# LNA_BFU500.net
KiCad netlist of a schematic drawn in Altium Designer
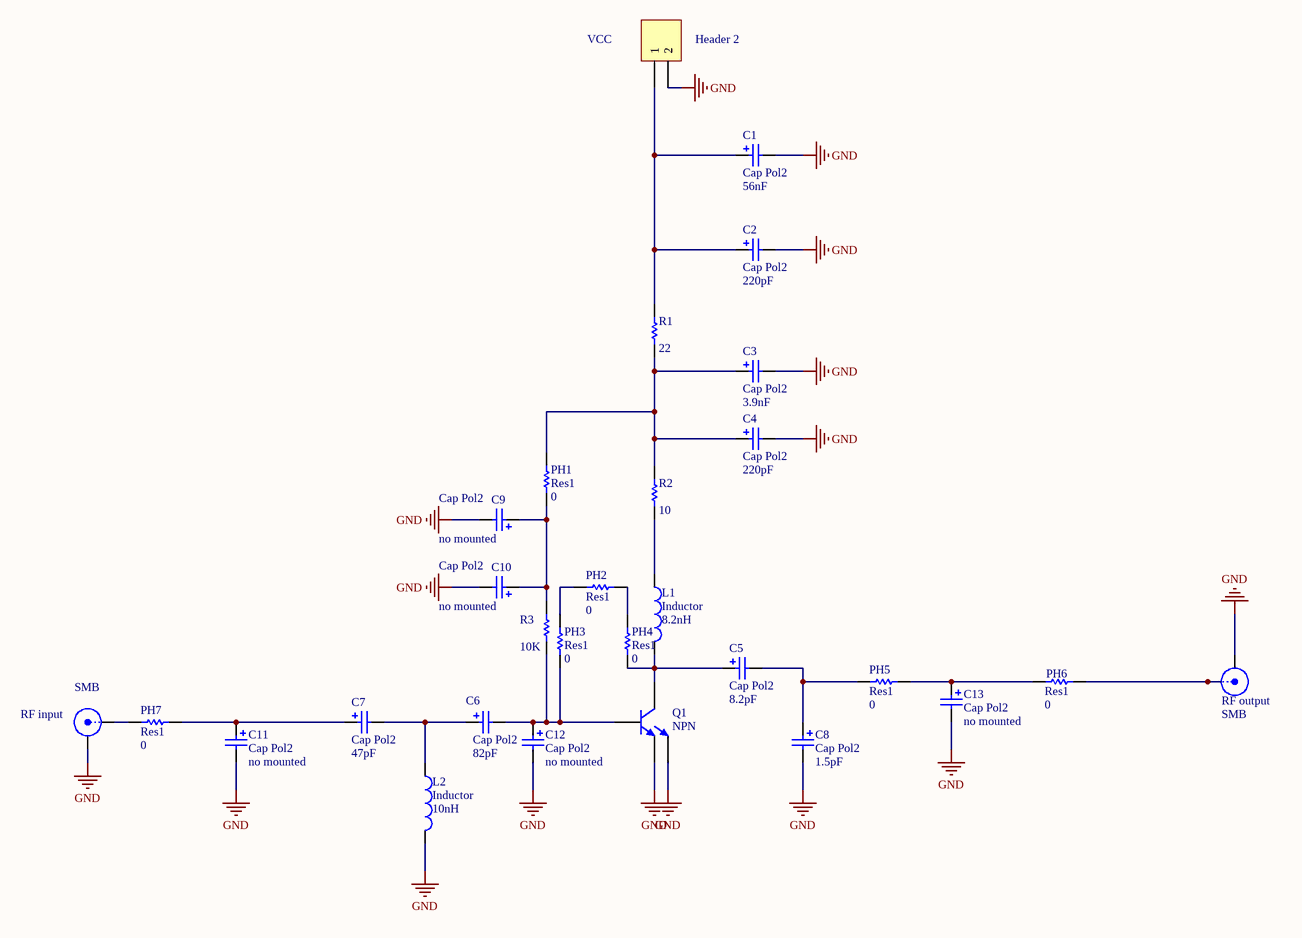
[diagram p0: LNA_BFU500.SchDoc]

(export (version "E")
  (design (tool "Eeschema 10.0.6"))
  (components
    (comp (ref "C1")
      (value "Cap Pol2")
      (footprint "6-0805_N")
      (description "Polarized Capacitor (Axial)")
      (fields (field (name "ALTIUM_VALUE") "56nF") (field (name "PUBLISHER") "Altium Limited"))
      (libsource (lib "PCB_Project") (part "Cap Pol2_1"))
    )
    (comp (ref "C2")
      (value "Cap Pol2")
      (footprint "6-0805_N")
      (description "Polarized Capacitor (Axial)")
      (fields (field (name "ALTIUM_VALUE") "220pF") (field (name "PUBLISHER") "Altium Limited"))
      (libsource (lib "PCB_Project") (part "Cap Pol2_1"))
    )
    (comp (ref "C3")
      (value "Cap Pol2")
      (footprint "6-0805_N")
      (description "Polarized Capacitor (Axial)")
      (fields (field (name "ALTIUM_VALUE") "3.9nF") (field (name "PUBLISHER") "Altium Limited"))
      (libsource (lib "PCB_Project") (part "Cap Pol2_1"))
    )
    (comp (ref "C4")
      (value "Cap Pol2")
      (footprint "6-0805_N")
      (description "Polarized Capacitor (Axial)")
      (fields (field (name "ALTIUM_VALUE") "220pF") (field (name "PUBLISHER") "Altium Limited"))
      (libsource (lib "PCB_Project") (part "Cap Pol2_1"))
    )
    (comp (ref "C5")
      (value "Cap Pol2")
      (footprint "6-0805_N")
      (description "Polarized Capacitor (Axial)")
      (fields (field (name "ALTIUM_VALUE") "8.2pF") (field (name "PUBLISHER") "Altium Limited"))
      (libsource (lib "PCB_Project") (part "Cap Pol2_1"))
    )
    (comp (ref "C6")
      (value "Cap Pol2")
      (footprint "6-0805_N")
      (description "Polarized Capacitor (Axial)")
      (fields (field (name "ALTIUM_VALUE") "82pF") (field (name "PUBLISHER") "Altium Limited"))
      (libsource (lib "PCB_Project") (part "Cap Pol2_1"))
    )
    (comp (ref "C7")
      (value "Cap Pol2")
      (footprint "6-0805_N")
      (description "Polarized Capacitor (Axial)")
      (fields (field (name "ALTIUM_VALUE") "47pF") (field (name "PUBLISHER") "Altium Limited"))
      (libsource (lib "PCB_Project") (part "Cap Pol2_1"))
    )
    (comp (ref "C8")
      (value "Cap Pol2")
      (footprint "6-0805_N")
      (description "Polarized Capacitor (Axial)")
      (fields (field (name "ALTIUM_VALUE") "1.5pF") (field (name "PUBLISHER") "Altium Limited"))
      (libsource (lib "PCB_Project") (part "Cap Pol2_1"))
    )
    (comp (ref "C9")
      (value "Cap Pol2")
      (footprint "6-0805_N")
      (description "Polarized Capacitor (Axial)")
      (fields (field (name "ALTIUM_VALUE") "no mounted") (field (name "PUBLISHER") "Altium Limited"))
      (libsource (lib "LNA_BFU550") (part "Cap Pol2_7"))
    )
    (comp (ref "C10")
      (value "Cap Pol2")
      (footprint "6-0805_N")
      (description "Polarized Capacitor (Axial)")
      (fields (field (name "ALTIUM_VALUE") "no mounted") (field (name "PUBLISHER") "Altium Limited"))
      (libsource (lib "LNA_BFU550") (part "Cap Pol2_7"))
    )
    (comp (ref "C11")
      (value "Cap Pol2")
      (footprint "6-0805_N")
      (description "Polarized Capacitor (Axial)")
      (fields (field (name "ALTIUM_VALUE") "no mounted") (field (name "PUBLISHER") "Altium Limited"))
      (libsource (lib "LNA_BFU550") (part "Cap Pol2_7"))
    )
    (comp (ref "C12")
      (value "Cap Pol2")
      (footprint "6-0805_N")
      (description "Polarized Capacitor (Axial)")
      (fields (field (name "ALTIUM_VALUE") "no mounted") (field (name "PUBLISHER") "Altium Limited"))
      (libsource (lib "LNA_BFU550") (part "Cap Pol2_7"))
    )
    (comp (ref "C13")
      (value "Cap Pol2")
      (footprint "6-0805_N")
      (description "Polarized Capacitor (Axial)")
      (fields (field (name "ALTIUM_VALUE") "no mounted") (field (name "PUBLISHER") "Altium Limited"))
      (libsource (lib "LNA_BFU550") (part "Cap Pol2_7"))
    )
    (comp (ref "L1")
      (value "Inductor")
      (footprint "6-0805_N")
      (fields (field (name "ALTIUM_VALUE") "8.2nH") (field (name "PUBLISHER") "Altium Limited"))
      (libsource (lib "PCB_Project") (part "Inductor"))
    )
    (comp (ref "L2")
      (value "Inductor")
      (footprint "6-0805_N")
      (fields (field (name "ALTIUM_VALUE") "10nH") (field (name "PUBLISHER") "Altium Limited"))
      (libsource (lib "PCB_Project") (part "Inductor"))
    )
    (comp (ref "PH1")
      (value "Res1")
      (footprint "6-0805_N")
      (description "Resistor")
      (fields (field (name "ALTIUM_VALUE") "0") (field (name "PUBLISHER") "Altium Limited"))
      (libsource (lib "LNA_BFU550") (part "Res1_1"))
    )
    (comp (ref "PH2")
      (value "Res1")
      (footprint "6-0805_N")
      (description "Resistor")
      (fields (field (name "ALTIUM_VALUE") "0") (field (name "PUBLISHER") "Altium Limited"))
      (libsource (lib "LNA_BFU550") (part "Res1_1"))
    )
    (comp (ref "PH3")
      (value "Res1")
      (footprint "6-0805_N")
      (description "Resistor")
      (fields (field (name "ALTIUM_VALUE") "0") (field (name "PUBLISHER") "Altium Limited"))
      (libsource (lib "LNA_BFU550") (part "Res1_1"))
    )
    (comp (ref "PH4")
      (value "Res1")
      (footprint "6-0805_N")
      (description "Resistor")
      (fields (field (name "ALTIUM_VALUE") "0") (field (name "PUBLISHER") "Altium Limited"))
      (libsource (lib "LNA_BFU550") (part "Res1_1"))
    )
    (comp (ref "PH5")
      (value "Res1")
      (footprint "6-0805_N")
      (description "Resistor")
      (fields (field (name "ALTIUM_VALUE") "0") (field (name "PUBLISHER") "Altium Limited"))
      (libsource (lib "LNA_BFU550") (part "Res1_1"))
    )
    (comp (ref "PH6")
      (value "Res1")
      (footprint "6-0805_N")
      (description "Resistor")
      (fields (field (name "ALTIUM_VALUE") "0") (field (name "PUBLISHER") "Altium Limited"))
      (libsource (lib "LNA_BFU550") (part "Res1_1"))
    )
    (comp (ref "PH7")
      (value "Res1")
      (footprint "6-0805_N")
      (description "Resistor")
      (fields (field (name "ALTIUM_VALUE") "0") (field (name "PUBLISHER") "Altium Limited"))
      (libsource (lib "LNA_BFU550") (part "Res1_1"))
    )
    (comp (ref "Q1")
      (value "NPN")
      (footprint "SOT-143_N")
      (description "NPN Bipolar Transistor")
      (fields (field (name "PUBLISHER") "Altium Limited"))
      (libsource (lib "LNA_BFU550") (part "NPN"))
    )
    (comp (ref "R1")
      (value "22")
      (footprint "6-0805_N")
      (description "Resistor")
      (fields (field (name "PUBLISHER") "Altium Limited"))
      (libsource (lib "PCB_Project") (part "Res1"))
    )
    (comp (ref "R2")
      (value "10")
      (footprint "6-0805_N")
      (description "Resistor")
      (fields (field (name "Comment") "0") (field (name "PUBLISHER") "Altium Limited"))
      (libsource (lib "PCB_Project") (part "Res1"))
    )
    (comp (ref "R3")
      (value "10K")
      (footprint "6-0805_N")
      (description "Resistor")
      (fields (field (name "Comment") "0") (field (name "PUBLISHER") "Altium Limited"))
      (libsource (lib "PCB_Project") (part "Res1"))
    )
    (comp (ref "RF input")
      (value "SMB")
      (footprint "SMA-142-0701-851_V2")
      (description "SMB Straight Connector")
      (fields (field (name "PUBLISHER") "Altium Limited"))
      (libsource (lib "PCB_Project") (part "SMB"))
    )
    (comp (ref "RF output")
      (value "SMB")
      (footprint "SMA-142-0701-851_V2")
      (description "SMB Straight Connector")
      (fields (field (name "PUBLISHER") "Altium Limited"))
      (libsource (lib "PCB_Project") (part "SMB"))
    )
    (comp (ref "VCC")
      (value "Header 2")
      (footprint "HDR1X2")
      (description "Header, 2-Pin")
      (fields (field (name "PUBLISHER") "Altium Limited"))
      (libsource (lib "PCB_Project") (part "Header 2"))
    )
  )
  (nets
    (net (code "1") (name "GND") (class "Default")
      (node (ref "C1") (pin "2") (pinfunction "2_2") (pintype "passive"))
      (node (ref "C10") (pin "2") (pinfunction "2_2") (pintype "passive"))
      (node (ref "C11") (pin "2") (pinfunction "2_2") (pintype "passive"))
      (node (ref "C12") (pin "2") (pinfunction "2_2") (pintype "passive"))
      (node (ref "C13") (pin "2") (pinfunction "2_2") (pintype "passive"))
      (node (ref "C2") (pin "2") (pinfunction "2_2") (pintype "passive"))
      (node (ref "C3") (pin "2") (pinfunction "2_2") (pintype "passive"))
      (node (ref "C4") (pin "2") (pinfunction "2_2") (pintype "passive"))
      (node (ref "C8") (pin "2") (pinfunction "2_2") (pintype "passive"))
      (node (ref "C9") (pin "2") (pinfunction "2_2") (pintype "passive"))
      (node (ref "L2") (pin "2") (pinfunction "2_2") (pintype "passive"))
      (node (ref "Q1") (pin "3") (pinfunction "E_3") (pintype "passive"))
      (node (ref "Q1") (pin "4") (pinfunction "E_4") (pintype "passive"))
      (node (ref "RF input") (pin "2") (pinfunction "Y_2") (pintype "passive"))
      (node (ref "RF output") (pin "2") (pinfunction "Y_2") (pintype "passive"))
      (node (ref "VCC") (pin "2") (pinfunction "2_2") (pintype "passive"))
    )
    (net (code "2") (name "Net-(C1-Pad1)") (class "Default")
      (node (ref "C1") (pin "1") (pinfunction "1_1") (pintype "passive"))
      (node (ref "C2") (pin "1") (pinfunction "1_1") (pintype "passive"))
      (node (ref "R1") (pin "2") (pinfunction "2_2") (pintype "passive"))
      (node (ref "VCC") (pin "1") (pinfunction "1_1") (pintype "passive"))
    )
    (net (code "3") (name "Net-(C3-Pad1)") (class "Default")
      (node (ref "C3") (pin "1") (pinfunction "1_1") (pintype "passive"))
      (node (ref "C4") (pin "1") (pinfunction "1_1") (pintype "passive"))
      (node (ref "PH1") (pin "2") (pinfunction "2_2") (pintype "passive"))
      (node (ref "R1") (pin "1") (pinfunction "1_1") (pintype "passive"))
      (node (ref "R2") (pin "2") (pinfunction "2_2") (pintype "passive"))
    )
    (net (code "4") (name "Net-(C5-Pad2)") (class "Default")
      (node (ref "C5") (pin "2") (pinfunction "2_2") (pintype "passive"))
      (node (ref "C8") (pin "1") (pinfunction "1_1") (pintype "passive"))
      (node (ref "PH5") (pin "1") (pinfunction "1_1") (pintype "passive"))
    )
    (net (code "5") (name "Net-(C6-Pad1)") (class "Default")
      (node (ref "C6") (pin "1") (pinfunction "1_1") (pintype "passive"))
      (node (ref "C7") (pin "2") (pinfunction "2_2") (pintype "passive"))
      (node (ref "L2") (pin "1") (pinfunction "1_1") (pintype "passive"))
    )
    (net (code "6") (name "Net-(C10-Pad1)") (class "Default")
      (node (ref "C10") (pin "1") (pinfunction "1_1") (pintype "passive"))
      (node (ref "C9") (pin "1") (pinfunction "1_1") (pintype "passive"))
      (node (ref "PH1") (pin "1") (pinfunction "1_1") (pintype "passive"))
      (node (ref "R3") (pin "2") (pinfunction "2_2") (pintype "passive"))
    )
    (net (code "7") (name "Net-(C11-Pad1)") (class "Default")
      (node (ref "C11") (pin "1") (pinfunction "1_1") (pintype "passive"))
      (node (ref "C7") (pin "1") (pinfunction "1_1") (pintype "passive"))
      (node (ref "PH7") (pin "2") (pinfunction "2_2") (pintype "passive"))
    )
    (net (code "8") (name "Net-(C13-Pad1)") (class "Default")
      (node (ref "C13") (pin "1") (pinfunction "1_1") (pintype "passive"))
      (node (ref "PH5") (pin "2") (pinfunction "2_2") (pintype "passive"))
      (node (ref "PH6") (pin "1") (pinfunction "1_1") (pintype "passive"))
    )
    (net (code "9") (name "Net-(L1-Pad1)") (class "Default")
      (node (ref "L1") (pin "1") (pinfunction "1_1") (pintype "passive"))
      (node (ref "R2") (pin "1") (pinfunction "1_1") (pintype "passive"))
    )
    (net (code "10") (name "Net-(PH2-Pad1)") (class "Default")
      (node (ref "PH2") (pin "1") (pinfunction "1_1") (pintype "passive"))
      (node (ref "PH3") (pin "2") (pinfunction "2_2") (pintype "passive"))
    )
    (net (code "11") (name "Net-(PH2-Pad2)") (class "Default")
      (node (ref "PH2") (pin "2") (pinfunction "2_2") (pintype "passive"))
      (node (ref "PH4") (pin "2") (pinfunction "2_2") (pintype "passive"))
    )
    (net (code "12") (name "Net-(Q1-B)") (class "Default")
      (node (ref "C12") (pin "1") (pinfunction "1_1") (pintype "passive"))
      (node (ref "C6") (pin "2") (pinfunction "2_2") (pintype "passive"))
      (node (ref "PH3") (pin "1") (pinfunction "1_1") (pintype "passive"))
      (node (ref "Q1") (pin "2") (pinfunction "B_2") (pintype "passive"))
      (node (ref "R3") (pin "1") (pinfunction "1_1") (pintype "passive"))
    )
    (net (code "13") (name "Net-(Q1-C)") (class "Default")
      (node (ref "C5") (pin "1") (pinfunction "1_1") (pintype "passive"))
      (node (ref "L1") (pin "2") (pinfunction "2_2") (pintype "passive"))
      (node (ref "PH4") (pin "1") (pinfunction "1_1") (pintype "passive"))
      (node (ref "Q1") (pin "1") (pinfunction "C_1") (pintype "passive"))
    )
    (net (code "14") (name "Net-(RF input-X)") (class "Default")
      (node (ref "PH7") (pin "1") (pinfunction "1_1") (pintype "passive"))
      (node (ref "RF input") (pin "1") (pinfunction "X_1") (pintype "passive"))
    )
    (net (code "15") (name "Net-(RF output-X)") (class "Default")
      (node (ref "PH6") (pin "2") (pinfunction "2_2") (pintype "passive"))
      (node (ref "RF output") (pin "1") (pinfunction "X_1") (pintype "passive"))
    )
  )
)
